# schematic.net
KiCad netlist of a schematic drawn in EasyEDA
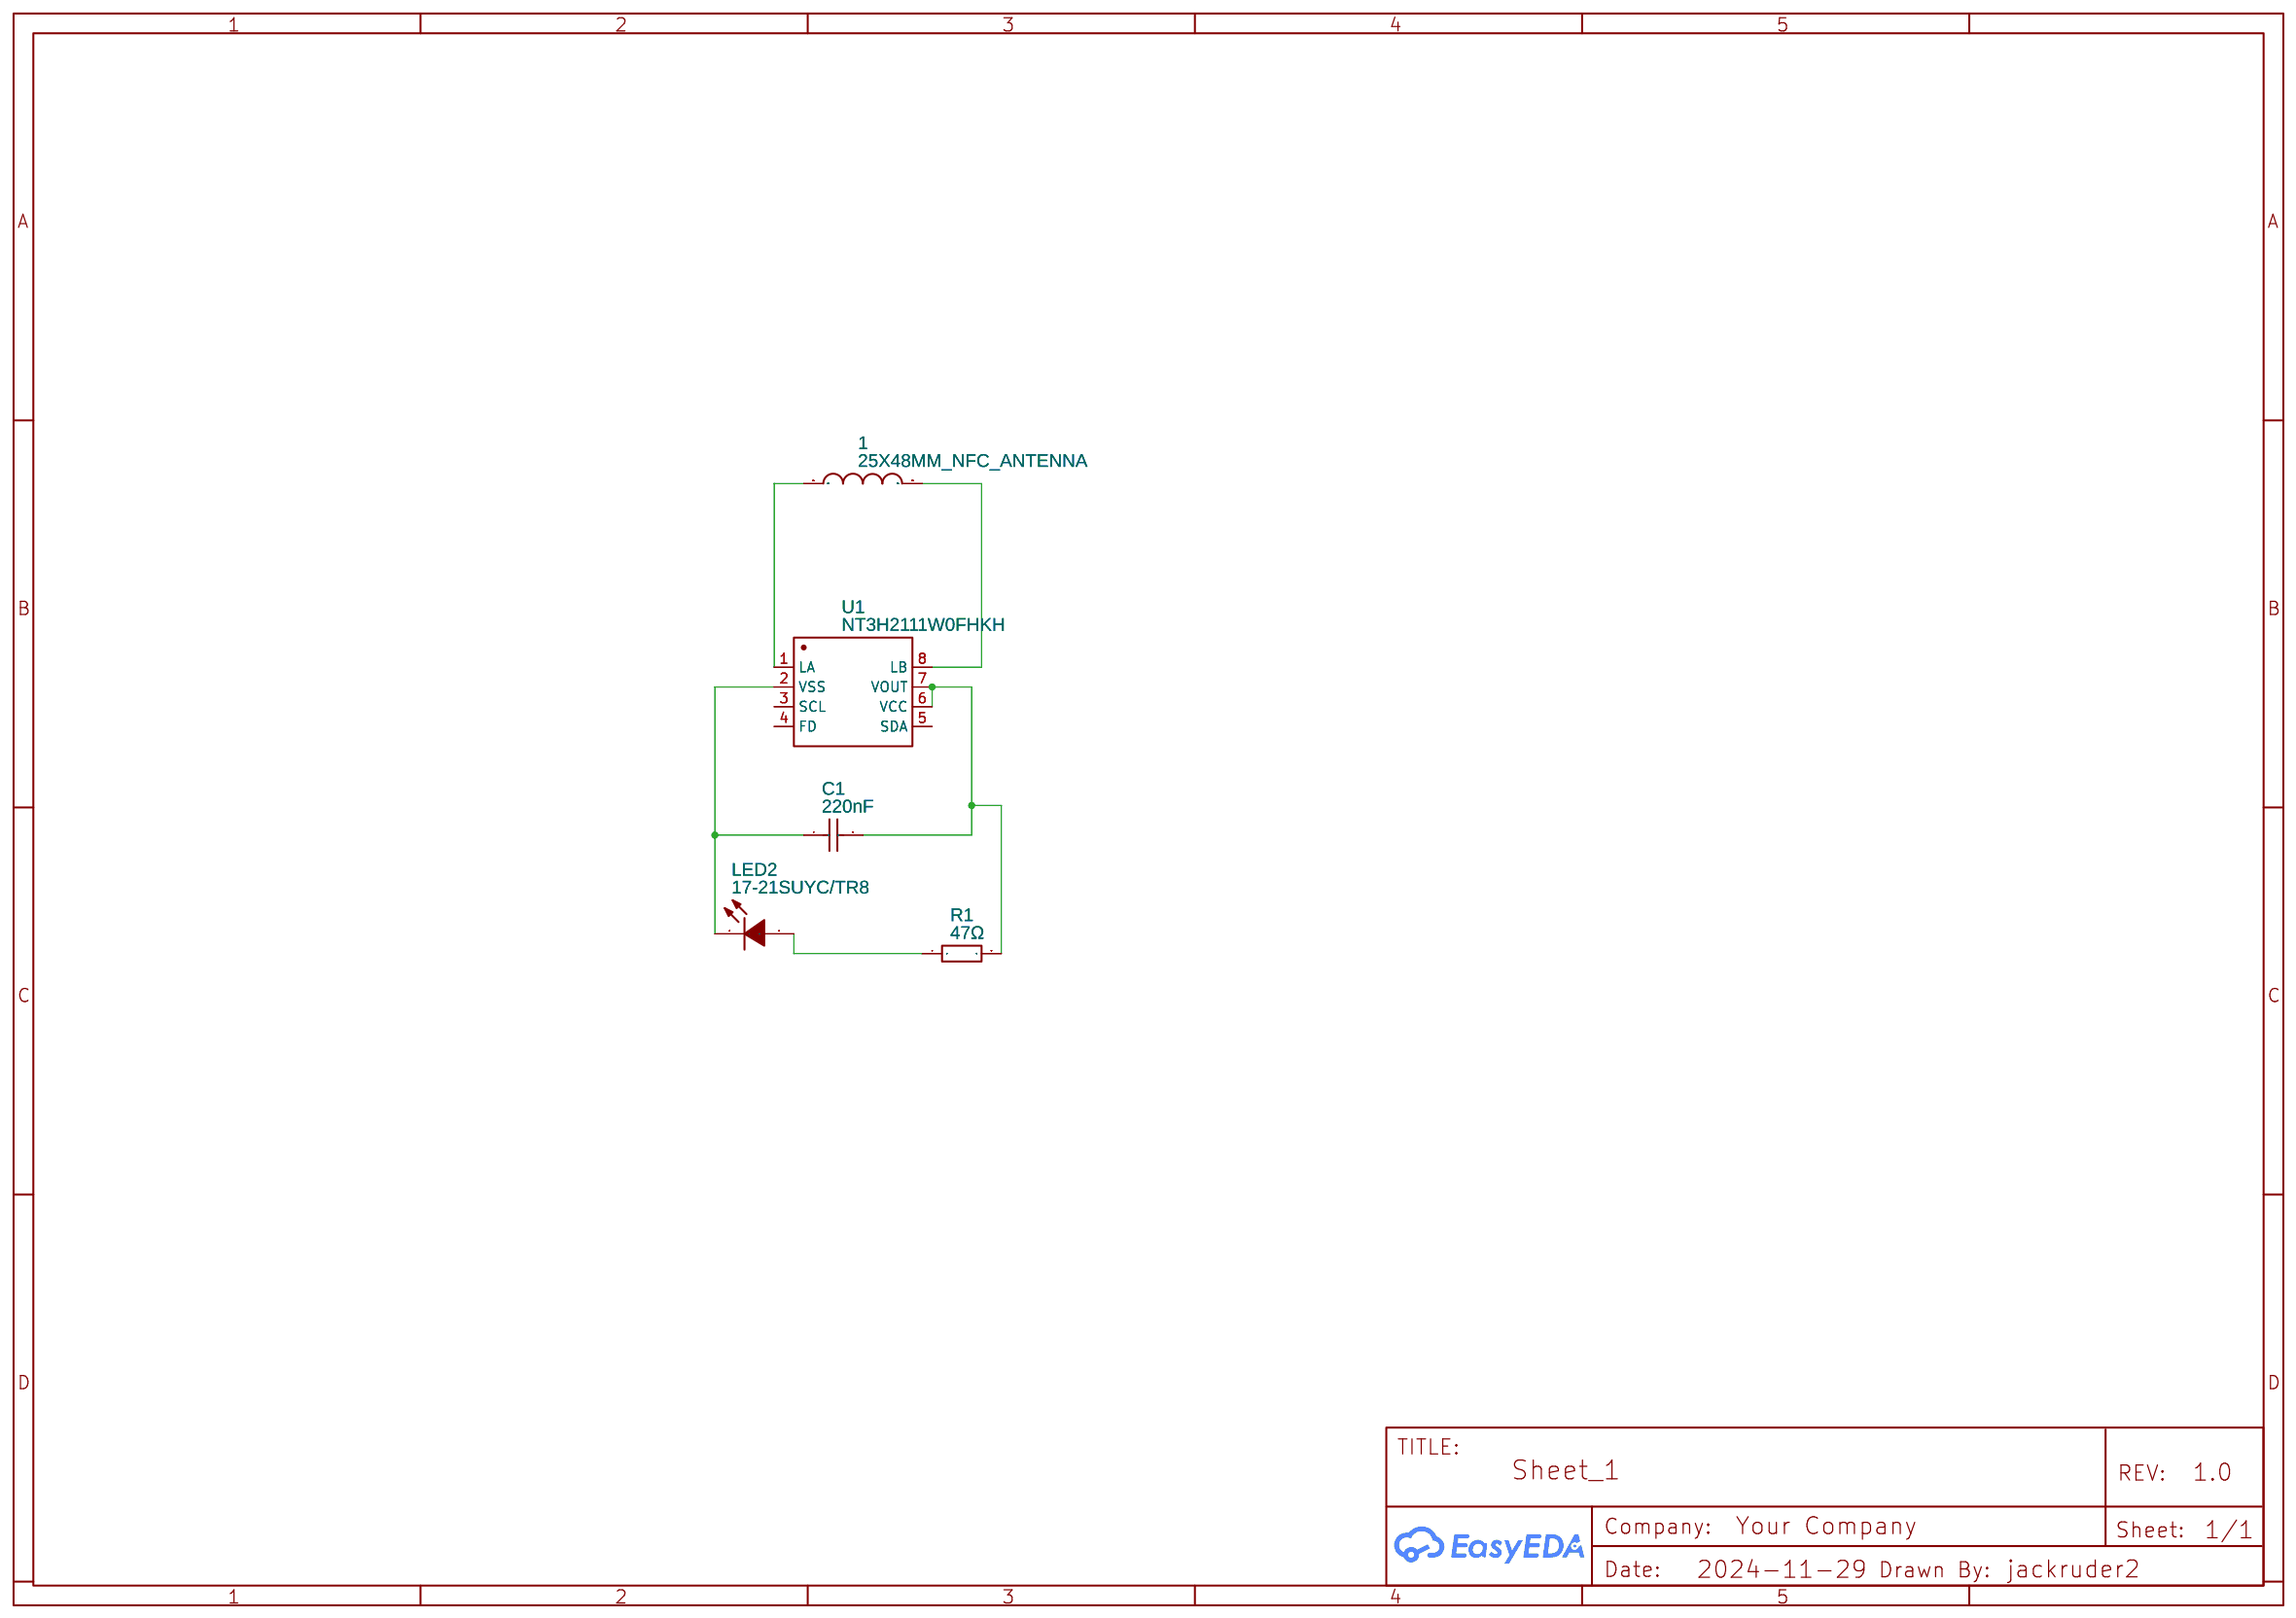
[diagram p0: schematic sheet]

(export (version "E")
  (design (tool "Eeschema 10.0.6"))
  (components
    (comp (ref "1") (value "25X48MM_NFC_ANTENNA") (libsource (lib "") (part "25X48MM_NFC_ANTENNA")))
    (comp (ref "C1")
      (value "220nF")
      (fields
        (field (name "Manufacturer Part") "CL10B224KA8NNNC")
        (field (name "Manufacturer") "SAMSUNG(三星)")
      )
      (libsource (lib "") (part "CL10B224KA8NNNC"))
    )
    (comp (ref "LED2")
      (value "17-21SUYC/TR8")
      (fields (field (name "Manufacturer Part") "KT-0805黄灯") (field (name "Manufacturer") "KENTO"))
      (libsource (lib "") (part "17-21SUYC/TR8"))
    )
    (comp (ref "R1")
      (value "47Ω")
      (fields
        (field (name "Manufacturer Part") "0603WAF470JT5E")
        (field (name "Manufacturer") "UNI-ROYAL(厚声)")
      )
      (libsource (lib "") (part "0603WAF470JT5E"))
    )
    (comp (ref "U1")
      (value "NT3H2111W0FHKH")
      (fields (field (name "Manufacturer") "NXP(恩智浦)"))
      (libsource (lib "") (part "NT3H2111W0FHKH"))
    )
  )
  (nets
    (net (code "1") (name "Net-(LED2-+)") (class "Default")
      (node (ref "LED2") (pin "1") (pinfunction "+_1") (pintype "unspecified"))
      (node (ref "R1") (pin "1") (pinfunction "1_1") (pintype "input"))
    )
    (net (code "2") (name "Net-(LED2--)") (class "Default")
      (node (ref "C1") (pin "1") (pinfunction "1_1") (pintype "input"))
      (node (ref "LED2") (pin "2") (pinfunction "-_2") (pintype "unspecified"))
      (node (ref "U1") (pin "2") (pinfunction "VSS_2") (pintype "unspecified"))
    )
    (net (code "3") (name "Net-(U1-LA)") (class "Default")
      (node (ref "1") (pin "P$1") (pinfunction "P$1_P$1") (pintype "bidirectional"))
      (node (ref "U1") (pin "1") (pinfunction "LA_1") (pintype "unspecified"))
    )
    (net (code "4") (name "Net-(U1-LB)") (class "Default")
      (node (ref "1") (pin "P$2") (pinfunction "P$2_P$2") (pintype "bidirectional"))
      (node (ref "U1") (pin "8") (pinfunction "LB_8") (pintype "unspecified"))
    )
    (net (code "5") (name "Net-(U1-VCC)") (class "Default")
      (node (ref "C1") (pin "2") (pinfunction "2_2") (pintype "input"))
      (node (ref "R1") (pin "2") (pinfunction "2_2") (pintype "input"))
      (node (ref "U1") (pin "6") (pinfunction "VCC_6") (pintype "unspecified"))
      (node (ref "U1") (pin "7") (pinfunction "VOUT_7") (pintype "unspecified"))
    )
    (net (code "6") (name "unconnected-(U1-FD-Pad4)") (class "Default")
      (node (ref "U1") (pin "4") (pinfunction "FD_4") (pintype "unspecified"))
    )
    (net (code "7") (name "unconnected-(U1-SCL-Pad3)") (class "Default")
      (node (ref "U1") (pin "3") (pinfunction "SCL_3") (pintype "unspecified"))
    )
    (net (code "8") (name "unconnected-(U1-SDA-Pad5)") (class "Default")
      (node (ref "U1") (pin "5") (pinfunction "SDA_5") (pintype "unspecified"))
    )
  )
)
